# Main_Board_Controller.net
KiCad netlist of a schematic drawn in Altium Designer
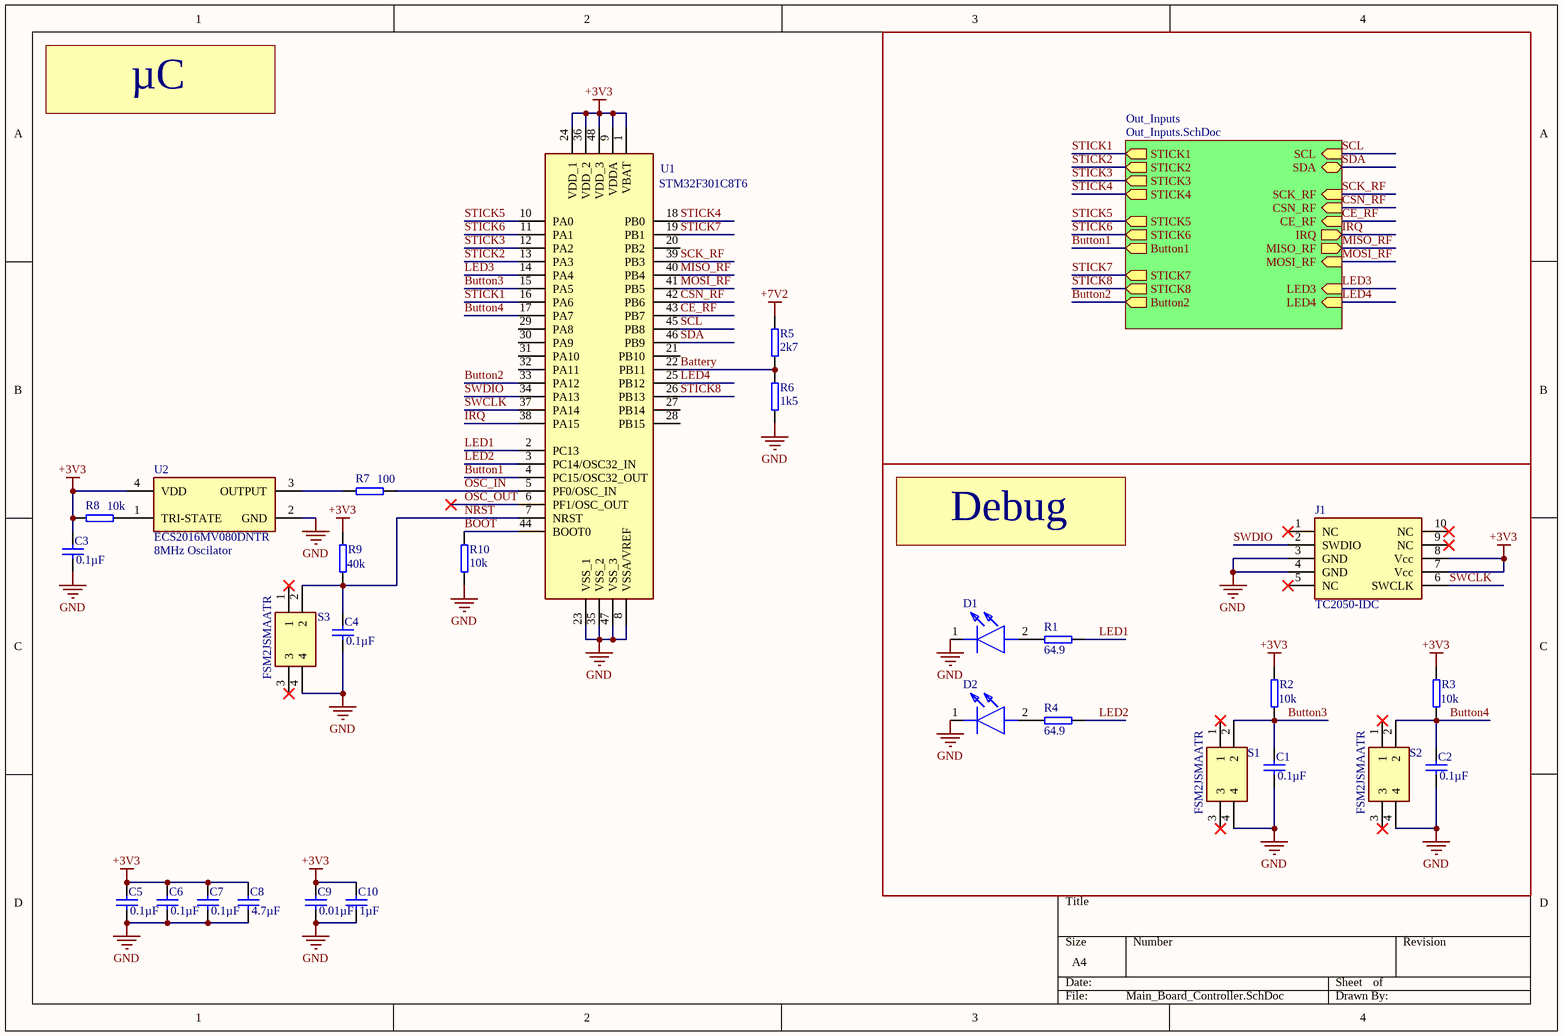
[diagram p0: Main_Board_Controller.SchDoc]

(export (version "E")
  (design (tool "Eeschema 10.0.6"))
  (components
    (comp (ref "C1")
      (value "0.1µF")
      (footprint "Capacitor 0603")
      (description "Capacitor")
      (libsource (lib "Schematic_Lib") (part "Capacitor 0603"))
    )
    (comp (ref "C2")
      (value "0.1µF")
      (footprint "Capacitor 0603")
      (description "Capacitor")
      (libsource (lib "Schematic_Lib") (part "Capacitor 0603"))
    )
    (comp (ref "C3")
      (value "0.1µF")
      (footprint "Capacitor 0603")
      (description "Capacitor")
      (libsource (lib "Schematic_Lib") (part "Capacitor 0603"))
    )
    (comp (ref "C4")
      (value "0.1µF")
      (footprint "Capacitor 0603")
      (description "Capacitor")
      (libsource (lib "Schematic_Lib") (part "Capacitor 0603"))
    )
    (comp (ref "C5")
      (value "0.1µF")
      (footprint "Capacitor 0603")
      (description "Capacitor")
      (libsource (lib "Schematic_Lib") (part "Capacitor 0603"))
    )
    (comp (ref "C6")
      (value "0.1µF")
      (footprint "Capacitor 0603")
      (description "Capacitor")
      (libsource (lib "Schematic_Lib") (part "Capacitor 0603"))
    )
    (comp (ref "C7")
      (value "0.1µF")
      (footprint "Capacitor 0603")
      (description "Capacitor")
      (libsource (lib "Schematic_Lib") (part "Capacitor 0603"))
    )
    (comp (ref "C8")
      (value "4.7µF")
      (footprint "Capacitor 0603")
      (description "Capacitor")
      (libsource (lib "Schematic_Lib") (part "Capacitor 0603"))
    )
    (comp (ref "C9")
      (value "0.01µF")
      (footprint "Capacitor 0603")
      (description "Capacitor")
      (libsource (lib "Schematic_Lib") (part "Capacitor 0603"))
    )
    (comp (ref "C10")
      (value "1µF")
      (footprint "Capacitor 0603")
      (description "Capacitor")
      (libsource (lib "Schematic_Lib") (part "Capacitor 0603"))
    )
    (comp (ref "D1")
      (value "LED 1608 (0603) SMD")
      (footprint "INS21AT2G")
      (libsource (lib "Schematic_Lib") (part "LED 1608 (0603) SMD"))
    )
    (comp (ref "D2")
      (value "LED 1608 (0603) SMD")
      (footprint "INS21AT2G")
      (libsource (lib "Schematic_Lib") (part "LED 1608 (0603) SMD"))
    )
    (comp (ref "J1")
      (value "TC2050-IDC")
      (footprint "TAG-CONNECT_TC2050-IDC")
      (description "CBL PLUG-OF-NAILS 10-PIN W/LEGS")
      (fields (field (name "MF") "Tag-Connect LLC") (field (name "DIGI-KEY_PART_NUMBER") "TC2050-IDC-ND"))
      (libsource (lib "Schematic_Lib") (part "TC2050-IDC"))
    )
    (comp (ref "R1")
      (value "64.9")
      (footprint "Resistor 0603")
      (description "Resistor")
      (libsource (lib "Schematic_Lib") (part "Resistor 0603"))
    )
    (comp (ref "R2")
      (value "10k")
      (footprint "Resistor 0603")
      (description "Resistor")
      (libsource (lib "Schematic_Lib") (part "Resistor 0603"))
    )
    (comp (ref "R3")
      (value "10k")
      (footprint "Resistor 0603")
      (description "Resistor")
      (libsource (lib "Schematic_Lib") (part "Resistor 0603"))
    )
    (comp (ref "R4")
      (value "64.9")
      (footprint "Resistor 0603")
      (description "Resistor")
      (libsource (lib "Schematic_Lib") (part "Resistor 0603"))
    )
    (comp (ref "R5")
      (value "2k7")
      (footprint "Resistor 0603")
      (description "Resistor")
      (libsource (lib "Schematic_Lib") (part "Resistor 0603"))
    )
    (comp (ref "R6")
      (value "1k5")
      (footprint "Resistor 0603")
      (description "Resistor")
      (libsource (lib "Schematic_Lib") (part "Resistor 0603"))
    )
    (comp (ref "R7")
      (value "100")
      (footprint "Resistor 0603")
      (description "Resistor")
      (libsource (lib "Schematic_Lib") (part "Resistor 0603"))
    )
    (comp (ref "R8")
      (value "10k")
      (footprint "Resistor 0603")
      (description "Resistor")
      (libsource (lib "Schematic_Lib") (part "Resistor 0603"))
    )
    (comp (ref "R9")
      (value "40k")
      (footprint "Resistor 0603")
      (description "Resistor")
      (libsource (lib "Schematic_Lib") (part "Resistor 0603"))
    )
    (comp (ref "R10")
      (value "10k")
      (footprint "Resistor 0603")
      (description "Resistor")
      (libsource (lib "Schematic_Lib") (part "Resistor 0603"))
    )
    (comp (ref "S1")
      (value "FSM2JSMAATR")
      (footprint "FSM2J_1")
      (description "Switch")
      (fields (field (name "MOUSER PART NUMBER") "506-FSM2JSMAATR"))
      (libsource (lib "Schematic_Lib") (part "FSM2JSMAATR"))
    )
    (comp (ref "S2")
      (value "FSM2JSMAATR")
      (footprint "FSM2J_1")
      (description "Switch")
      (fields (field (name "MOUSER PART NUMBER") "506-FSM2JSMAATR"))
      (libsource (lib "Schematic_Lib") (part "FSM2JSMAATR"))
    )
    (comp (ref "S3")
      (value "FSM2JSMAATR")
      (footprint "FSM2J_1")
      (description "Switch")
      (fields (field (name "MOUSER PART NUMBER") "506-FSM2JSMAATR"))
      (libsource (lib "Schematic_Lib") (part "FSM2JSMAATR"))
    )
    (comp (ref "U1")
      (value "STM32F301C8T6")
      (footprint "QFP50P900X900X160-48N")
      (description "STMICROELECTRONICS - STM32F301C8T6 - MCU, 32BIT, CORTEX-M4, 72MHZ, LQFP-48")
      (fields (field (name "MOUSER PART NUMBER") "511-STM32F301C8T6"))
      (libsource (lib "Schematic_Lib") (part "STM32F301C8T6"))
    )
    (comp (ref "U2")
      (value "ECS2016MV080DNTR")
      (footprint "OSC_ECS-1618-300-BN-TR")
      (description "25 MHz XO (Standard) HCMOS Oscillator 1.8V ~ 3.3V Enable/Disable 4-SMD, No Lead")
      (fields (field (name "MF") "ECS Inc.") (field (name "MP") "ECS-2016MV-250-CN-TR3"))
      (libsource (lib "Schematic_Lib") (part "ECS-2016MV-250-CN-TR3"))
    )
  )
  (nets
    (net (code "1") (name "+3V3") (class "Default")
      (node (ref "C10") (pin "1") (pinfunction "1_1") (pintype "passive"))
      (node (ref "C3") (pin "1") (pinfunction "1_1") (pintype "passive"))
      (node (ref "C5") (pin "1") (pinfunction "1_1") (pintype "passive"))
      (node (ref "C6") (pin "1") (pinfunction "1_1") (pintype "passive"))
      (node (ref "C7") (pin "1") (pinfunction "1_1") (pintype "passive"))
      (node (ref "C8") (pin "1") (pinfunction "1_1") (pintype "passive"))
      (node (ref "C9") (pin "1") (pinfunction "1_1") (pintype "passive"))
      (node (ref "J1") (pin "7") (pinfunction "Vcc_7") (pintype "passive"))
      (node (ref "J1") (pin "8") (pinfunction "Vcc_8") (pintype "passive"))
      (node (ref "R2") (pin "1") (pintype "passive"))
      (node (ref "R3") (pin "1") (pintype "passive"))
      (node (ref "R8") (pin "2") (pintype "passive"))
      (node (ref "R9") (pin "1") (pintype "passive"))
      (node (ref "U1") (pin "1") (pinfunction "VBAT_1") (pintype "passive"))
      (node (ref "U1") (pin "24") (pinfunction "VDD_1_24") (pintype "passive"))
      (node (ref "U1") (pin "36") (pinfunction "VDD_2_36") (pintype "passive"))
      (node (ref "U1") (pin "48") (pinfunction "VDD_3_48") (pintype "passive"))
      (node (ref "U1") (pin "9") (pinfunction "VDDA_9") (pintype "passive"))
      (node (ref "U2") (pin "4") (pinfunction "VDD_4") (pintype "passive"))
    )
    (net (code "2") (name "+7V2") (class "Default") (node (ref "R5") (pin "2") (pintype "passive")))
    (net (code "3") (name "/BOOT") (class "Default")
      (node (ref "R10") (pin "2") (pintype "passive"))
      (node (ref "U1") (pin "44") (pinfunction "BOOT0_44") (pintype "passive"))
    )
    (net (code "4") (name "/Battery") (class "Default")
      (node (ref "R5") (pin "1") (pintype "passive"))
      (node (ref "R6") (pin "2") (pintype "passive"))
      (node (ref "U1") (pin "22") (pinfunction "PB11_22") (pintype "passive"))
    )
    (net (code "5") (name "/Button1") (class "Default")
      (node (ref "U1") (pin "4") (pinfunction "PC15/OSC32_OUT_4") (pintype "passive"))
    )
    (net (code "6") (name "/Button2") (class "Default")
      (node (ref "U1") (pin "33") (pinfunction "PA12_33") (pintype "passive"))
    )
    (net (code "7") (name "/Button3") (class "Default")
      (node (ref "C1") (pin "1") (pinfunction "1_1") (pintype "passive"))
      (node (ref "R2") (pin "2") (pintype "passive"))
      (node (ref "S1") (pin "2") (pinfunction "2_2") (pintype "passive"))
      (node (ref "U1") (pin "15") (pinfunction "PA5_15") (pintype "passive"))
    )
    (net (code "8") (name "/Button4") (class "Default")
      (node (ref "C2") (pin "1") (pinfunction "1_1") (pintype "passive"))
      (node (ref "R3") (pin "2") (pintype "passive"))
      (node (ref "S2") (pin "2") (pinfunction "2_2") (pintype "passive"))
      (node (ref "U1") (pin "17") (pinfunction "PA7_17") (pintype "passive"))
    )
    (net (code "9") (name "/CE_RF") (class "Default")
      (node (ref "U1") (pin "43") (pinfunction "PB7_43") (pintype "passive"))
    )
    (net (code "10") (name "/CSN_RF") (class "Default")
      (node (ref "U1") (pin "42") (pinfunction "PB6_42") (pintype "passive"))
    )
    (net (code "11") (name "/IRQ") (class "Default")
      (node (ref "U1") (pin "38") (pinfunction "PA15_38") (pintype "passive"))
    )
    (net (code "12") (name "/LED1") (class "Default")
      (node (ref "R1") (pin "1") (pintype "passive"))
      (node (ref "U1") (pin "2") (pinfunction "PC13_2") (pintype "passive"))
    )
    (net (code "13") (name "/LED2") (class "Default")
      (node (ref "R4") (pin "1") (pintype "passive"))
      (node (ref "U1") (pin "3") (pinfunction "PC14/OSC32_IN_3") (pintype "passive"))
    )
    (net (code "14") (name "/LED3") (class "Default")
      (node (ref "U1") (pin "14") (pinfunction "PA4_14") (pintype "passive"))
    )
    (net (code "15") (name "/LED4") (class "Default")
      (node (ref "U1") (pin "25") (pinfunction "PB12_25") (pintype "passive"))
    )
    (net (code "16") (name "/MISO_RF") (class "Default")
      (node (ref "U1") (pin "40") (pinfunction "PB4_40") (pintype "passive"))
    )
    (net (code "17") (name "/MOSI_RF") (class "Default")
      (node (ref "U1") (pin "41") (pinfunction "PB5_41") (pintype "passive"))
    )
    (net (code "18") (name "/NRST") (class "Default")
      (node (ref "C4") (pin "1") (pinfunction "1_1") (pintype "passive"))
      (node (ref "R9") (pin "2") (pintype "passive"))
      (node (ref "S3") (pin "2") (pinfunction "2_2") (pintype "passive"))
      (node (ref "U1") (pin "7") (pinfunction "NRST_7") (pintype "passive"))
    )
    (net (code "19") (name "/OSC_IN") (class "Default")
      (node (ref "R7") (pin "1") (pintype "passive"))
      (node (ref "U1") (pin "5") (pinfunction "PF0/OSC_IN_5") (pintype "passive"))
    )
    (net (code "20") (name "/OSC_OUT") (class "Default")
      (node (ref "U1") (pin "6") (pinfunction "PF1/OSC_OUT_6") (pintype "passive+no_connect"))
    )
    (net (code "21") (name "/SCK_RF") (class "Default")
      (node (ref "U1") (pin "39") (pinfunction "PB3_39") (pintype "passive"))
    )
    (net (code "22") (name "/SCL") (class "Default")
      (node (ref "U1") (pin "45") (pinfunction "PB8_45") (pintype "passive"))
    )
    (net (code "23") (name "/SDA") (class "Default")
      (node (ref "U1") (pin "46") (pinfunction "PB9_46") (pintype "passive"))
    )
    (net (code "24") (name "/STICK1") (class "Default")
      (node (ref "U1") (pin "16") (pinfunction "PA6_16") (pintype "passive"))
    )
    (net (code "25") (name "/STICK2") (class "Default")
      (node (ref "U1") (pin "13") (pinfunction "PA3_13") (pintype "passive"))
    )
    (net (code "26") (name "/STICK3") (class "Default")
      (node (ref "U1") (pin "12") (pinfunction "PA2_12") (pintype "passive"))
    )
    (net (code "27") (name "/STICK4") (class "Default")
      (node (ref "U1") (pin "18") (pinfunction "PB0_18") (pintype "passive"))
    )
    (net (code "28") (name "/STICK5") (class "Default")
      (node (ref "U1") (pin "10") (pinfunction "PA0_10") (pintype "passive"))
    )
    (net (code "29") (name "/STICK6") (class "Default")
      (node (ref "U1") (pin "11") (pinfunction "PA1_11") (pintype "passive"))
    )
    (net (code "30") (name "/STICK7") (class "Default")
      (node (ref "U1") (pin "19") (pinfunction "PB1_19") (pintype "passive"))
    )
    (net (code "31") (name "/STICK8") (class "Default")
      (node (ref "U1") (pin "26") (pinfunction "PB13_26") (pintype "passive"))
    )
    (net (code "32") (name "/SWCLK") (class "Default")
      (node (ref "J1") (pin "6") (pinfunction "SWCLK_6") (pintype "passive"))
      (node (ref "U1") (pin "37") (pinfunction "PA14_37") (pintype "passive"))
    )
    (net (code "33") (name "/SWDIO") (class "Default")
      (node (ref "J1") (pin "2") (pinfunction "SWDIO_2") (pintype "passive"))
      (node (ref "U1") (pin "34") (pinfunction "PA13_34") (pintype "passive"))
    )
    (net (code "34") (name "GND") (class "Default")
      (node (ref "C1") (pin "2") (pinfunction "2_2") (pintype "passive"))
      (node (ref "C10") (pin "2") (pinfunction "2_2") (pintype "passive"))
      (node (ref "C2") (pin "2") (pinfunction "2_2") (pintype "passive"))
      (node (ref "C3") (pin "2") (pinfunction "2_2") (pintype "passive"))
      (node (ref "C4") (pin "2") (pinfunction "2_2") (pintype "passive"))
      (node (ref "C5") (pin "2") (pinfunction "2_2") (pintype "passive"))
      (node (ref "C6") (pin "2") (pinfunction "2_2") (pintype "passive"))
      (node (ref "C7") (pin "2") (pinfunction "2_2") (pintype "passive"))
      (node (ref "C8") (pin "2") (pinfunction "2_2") (pintype "passive"))
      (node (ref "C9") (pin "2") (pinfunction "2_2") (pintype "passive"))
      (node (ref "D1") (pin "1") (pinfunction "K_1") (pintype "passive"))
      (node (ref "D2") (pin "1") (pinfunction "K_1") (pintype "passive"))
      (node (ref "J1") (pin "3") (pinfunction "GND_3") (pintype "passive"))
      (node (ref "J1") (pin "4") (pinfunction "GND_4") (pintype "passive"))
      (node (ref "R10") (pin "1") (pintype "passive"))
      (node (ref "R6") (pin "1") (pintype "passive"))
      (node (ref "S1") (pin "4") (pinfunction "4_4") (pintype "passive"))
      (node (ref "S2") (pin "4") (pinfunction "4_4") (pintype "passive"))
      (node (ref "S3") (pin "4") (pinfunction "4_4") (pintype "passive"))
      (node (ref "U1") (pin "23") (pinfunction "VSS_1_23") (pintype "passive"))
      (node (ref "U1") (pin "35") (pinfunction "VSS_2_35") (pintype "passive"))
      (node (ref "U1") (pin "47") (pinfunction "VSS_3_47") (pintype "passive"))
      (node (ref "U1") (pin "8") (pinfunction "VSSA/VREF_8") (pintype "passive"))
      (node (ref "U2") (pin "2") (pinfunction "GND_2") (pintype "power_in"))
    )
    (net (code "35") (name "Net-(D1-A)") (class "Default")
      (node (ref "D1") (pin "2") (pinfunction "A_2") (pintype "passive"))
      (node (ref "R1") (pin "2") (pintype "passive"))
    )
    (net (code "36") (name "Net-(D2-A)") (class "Default")
      (node (ref "D2") (pin "2") (pinfunction "A_2") (pintype "passive"))
      (node (ref "R4") (pin "2") (pintype "passive"))
    )
    (net (code "37") (name "Net-(U2-OUTPUT)") (class "Default")
      (node (ref "R7") (pin "2") (pintype "passive"))
      (node (ref "U2") (pin "3") (pinfunction "OUTPUT_3") (pintype "passive"))
    )
    (net (code "38") (name "Net-(U2-TRI-STATE)") (class "Default")
      (node (ref "R8") (pin "1") (pintype "passive"))
      (node (ref "U2") (pin "1") (pinfunction "TRI-STATE_1") (pintype "passive"))
    )
    (net (code "39") (name "unconnected-(J1-NC-Pad1)") (class "Default")
      (node (ref "J1") (pin "1") (pinfunction "NC_1") (pintype "passive+no_connect"))
    )
    (net (code "40") (name "unconnected-(J1-NC-Pad5)") (class "Default")
      (node (ref "J1") (pin "5") (pinfunction "NC_5") (pintype "passive+no_connect"))
    )
    (net (code "41") (name "unconnected-(J1-NC-Pad9)") (class "Default")
      (node (ref "J1") (pin "9") (pinfunction "NC_9") (pintype "passive+no_connect"))
    )
    (net (code "42") (name "unconnected-(J1-NC-Pad10)") (class "Default")
      (node (ref "J1") (pin "10") (pinfunction "NC_10") (pintype "passive+no_connect"))
    )
    (net (code "43") (name "unconnected-(S1-Pad1)") (class "Default")
      (node (ref "S1") (pin "1") (pinfunction "1_1") (pintype "passive+no_connect"))
    )
    (net (code "44") (name "unconnected-(S1-Pad3)") (class "Default")
      (node (ref "S1") (pin "3") (pinfunction "3_3") (pintype "passive+no_connect"))
    )
    (net (code "45") (name "unconnected-(S2-Pad1)") (class "Default")
      (node (ref "S2") (pin "1") (pinfunction "1_1") (pintype "passive+no_connect"))
    )
    (net (code "46") (name "unconnected-(S2-Pad3)") (class "Default")
      (node (ref "S2") (pin "3") (pinfunction "3_3") (pintype "passive+no_connect"))
    )
    (net (code "47") (name "unconnected-(S3-Pad1)") (class "Default")
      (node (ref "S3") (pin "1") (pinfunction "1_1") (pintype "passive+no_connect"))
    )
    (net (code "48") (name "unconnected-(S3-Pad3)") (class "Default")
      (node (ref "S3") (pin "3") (pinfunction "3_3") (pintype "passive+no_connect"))
    )
    (net (code "49") (name "unconnected-(U1-PA8-Pad29)") (class "Default")
      (node (ref "U1") (pin "29") (pinfunction "PA8_29") (pintype "passive"))
    )
    (net (code "50") (name "unconnected-(U1-PA9-Pad30)") (class "Default")
      (node (ref "U1") (pin "30") (pinfunction "PA9_30") (pintype "passive"))
    )
    (net (code "51") (name "unconnected-(U1-PA10-Pad31)") (class "Default")
      (node (ref "U1") (pin "31") (pinfunction "PA10_31") (pintype "passive"))
    )
    (net (code "52") (name "unconnected-(U1-PA11-Pad32)") (class "Default")
      (node (ref "U1") (pin "32") (pinfunction "PA11_32") (pintype "passive"))
    )
    (net (code "53") (name "unconnected-(U1-PB2-Pad20)") (class "Default")
      (node (ref "U1") (pin "20") (pinfunction "PB2_20") (pintype "passive"))
    )
    (net (code "54") (name "unconnected-(U1-PB10-Pad21)") (class "Default")
      (node (ref "U1") (pin "21") (pinfunction "PB10_21") (pintype "passive"))
    )
    (net (code "55") (name "unconnected-(U1-PB14-Pad27)") (class "Default")
      (node (ref "U1") (pin "27") (pinfunction "PB14_27") (pintype "passive"))
    )
    (net (code "56") (name "unconnected-(U1-PB15-Pad28)") (class "Default")
      (node (ref "U1") (pin "28") (pinfunction "PB15_28") (pintype "passive"))
    )
  )
)
